# Channel_Power.net
KiCad netlist of a schematic drawn in Altium Designer
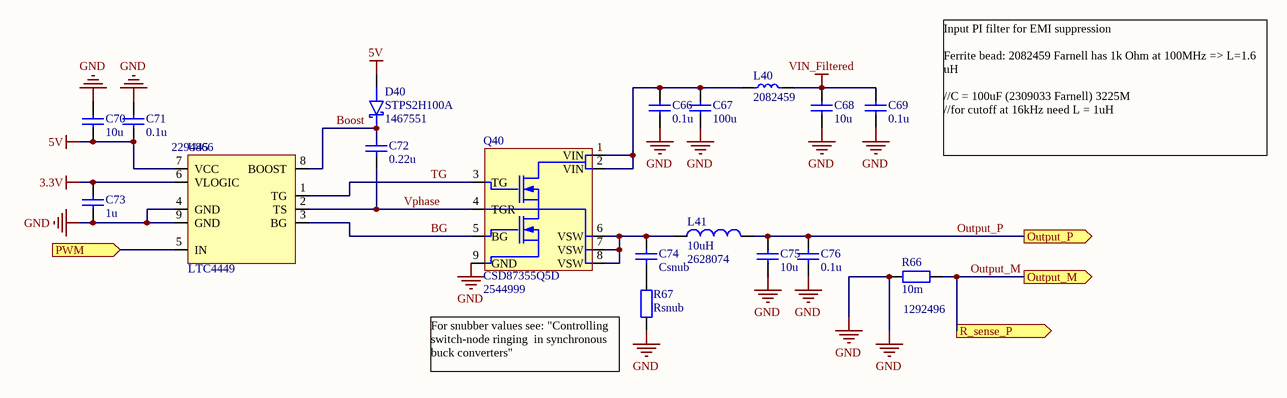
[diagram p0: Channel_Power.SchDoc]

(export (version "E")
  (design (tool "Eeschema 10.0.6"))
  (components
    (comp (ref "C66") (value "0.1u") (footprint "CAPC1608M") (libsource (lib "Passives") (part "C")))
    (comp (ref "C67") (value "100u") (footprint "CAPC3225M") (libsource (lib "Passives") (part "C")))
    (comp (ref "C68") (value "10u") (footprint "CAPC2012M") (libsource (lib "Passives") (part "C")))
    (comp (ref "C69") (value "0.1u") (footprint "CAPC1608M") (libsource (lib "Passives") (part "C")))
    (comp (ref "C70") (value "10u") (footprint "CAPC2012M") (libsource (lib "Passives") (part "C")))
    (comp (ref "C71") (value "0.1u") (footprint "CAPC1608M") (libsource (lib "Passives") (part "C")))
    (comp (ref "C72") (value "0.22u") (footprint "CAPC1608M") (libsource (lib "Passives") (part "C")))
    (comp (ref "C73") (value "1u") (footprint "CAPC1608M") (libsource (lib "Passives") (part "C")))
    (comp (ref "C74") (value "Csnub") (footprint "CAPC1608M") (libsource (lib "Passives") (part "C")))
    (comp (ref "C75") (value "10u") (footprint "CAPC2012M") (libsource (lib "Passives") (part "C")))
    (comp (ref "C76") (value "0.1u") (footprint "CAPC1608M") (libsource (lib "Passives") (part "C")))
    (comp (ref "D40")
      (value "STPS2H100A")
      (footprint "DSO-C2/X1.8")
      (description "Shottky rectifier")
      (fields (field (name "SUPPLIER PART NUMBER 1") "1467551"))
      (libsource (lib "Diodes") (part "STPS2H100A"))
    )
    (comp (ref "L40")
      (value "Wurth_742792901")
      (footprint "WE_742792901")
      (description "Ferrite bead, 1.1k Ohm, 10A, (Wurth 742792901)")
      (fields (field (name "SUPPLIER PART NUMBER 1") "2082459"))
      (libsource (lib "Passives") (part "Wurth_742792901"))
    )
    (comp (ref "L41")
      (value "10uH")
      (footprint "L_XAL1510")
      (description "XAL1510 Series inductor")
      (fields (field (name "SUPPLIER PART NUMBER 1") "2628074"))
      (libsource (lib "Passives") (part "L_XAL1510"))
    )
    (comp (ref "Q40")
      (value "CSD87355Q5D")
      (footprint "SON-8")
      (description "Synchronous Buck NexFET Power Block")
      (fields (field (name "SUPPLIER PART NUMBER 1") "2544999"))
      (libsource (lib "Linear") (part "CSD87355Q5D"))
    )
    (comp (ref "R66") (value "10m") (footprint "RESC6432M") (libsource (lib "Passives") (part "R")))
    (comp (ref "R67") (value "Rsnub") (footprint "RESC1608M") (libsource (lib "Passives") (part "R")))
    (comp (ref "U45")
      (value "LTC4449")
      (footprint "DFN-8")
      (description "High Speed Synchronous N-Channel MOSFET Driver")
      (fields (field (name "SUPPLIER PART NUMBER 1") "2294866"))
      (libsource (lib "Controllers") (part "LTC4449"))
    )
  )
  (nets
    (net (code "1") (name "/BG") (class "Default")
      (node (ref "Q40") (pin "5") (pinfunction "BG_5") (pintype "passive"))
      (node (ref "U45") (pin "3") (pinfunction "BG_3") (pintype "passive"))
    )
    (net (code "2") (name "/Boost") (class "Default")
      (node (ref "C72") (pin "1") (pinfunction "1_1") (pintype "passive"))
      (node (ref "D40") (pin "C") (pinfunction "C_C") (pintype "passive"))
      (node (ref "U45") (pin "8") (pinfunction "BOOST_8") (pintype "passive"))
    )
    (net (code "3") (name "/Output_M") (class "Default")
      (node (ref "R66") (pin "2") (pinfunction "2_2") (pintype "passive"))
    )
    (net (code "4") (name "/Output_P") (class "Default")
      (node (ref "C75") (pin "1") (pinfunction "1_1") (pintype "passive"))
      (node (ref "C76") (pin "1") (pinfunction "1_1") (pintype "passive"))
      (node (ref "L41") (pin "1") (pintype "passive"))
    )
    (net (code "5") (name "/PWM") (class "Default")
      (node (ref "U45") (pin "5") (pinfunction "IN_5") (pintype "passive"))
    )
    (net (code "6") (name "/TG") (class "Default")
      (node (ref "Q40") (pin "3") (pinfunction "TG_3") (pintype "passive"))
      (node (ref "U45") (pin "1") (pinfunction "TG_1") (pintype "passive"))
    )
    (net (code "7") (name "/Vphase") (class "Default")
      (node (ref "C72") (pin "2") (pinfunction "2_2") (pintype "passive"))
      (node (ref "Q40") (pin "4") (pinfunction "TGR_4") (pintype "passive"))
      (node (ref "U45") (pin "2") (pinfunction "TS_2") (pintype "passive"))
    )
    (net (code "8") (name "3.3V") (class "Default")
      (node (ref "C73") (pin "1") (pinfunction "1_1") (pintype "passive"))
      (node (ref "U45") (pin "6") (pinfunction "VLOGIC_6") (pintype "passive"))
    )
    (net (code "9") (name "5V") (class "Default")
      (node (ref "C70") (pin "2") (pinfunction "2_2") (pintype "passive"))
      (node (ref "C71") (pin "2") (pinfunction "2_2") (pintype "passive"))
      (node (ref "D40") (pin "A") (pinfunction "A_A") (pintype "passive"))
      (node (ref "U45") (pin "7") (pinfunction "VCC_7") (pintype "passive"))
    )
    (net (code "10") (name "GND") (class "Default")
      (node (ref "C66") (pin "2") (pinfunction "2_2") (pintype "passive"))
      (node (ref "C67") (pin "2") (pinfunction "2_2") (pintype "passive"))
      (node (ref "C68") (pin "2") (pinfunction "2_2") (pintype "passive"))
      (node (ref "C69") (pin "2") (pinfunction "2_2") (pintype "passive"))
      (node (ref "C70") (pin "1") (pinfunction "1_1") (pintype "passive"))
      (node (ref "C71") (pin "1") (pinfunction "1_1") (pintype "passive"))
      (node (ref "C73") (pin "2") (pinfunction "2_2") (pintype "passive"))
      (node (ref "C75") (pin "2") (pinfunction "2_2") (pintype "passive"))
      (node (ref "C76") (pin "2") (pinfunction "2_2") (pintype "passive"))
      (node (ref "Q40") (pin "9") (pinfunction "GND_9") (pintype "passive"))
      (node (ref "R66") (pin "1") (pinfunction "1_1") (pintype "passive"))
      (node (ref "R67") (pin "1") (pinfunction "1_1") (pintype "passive"))
      (node (ref "U45") (pin "4") (pinfunction "GND_4") (pintype "passive"))
      (node (ref "U45") (pin "9") (pinfunction "GND_9") (pintype "passive"))
    )
    (net (code "11") (name "Net-(C66-Pad1)") (class "Default")
      (node (ref "C66") (pin "1") (pinfunction "1_1") (pintype "passive"))
      (node (ref "C67") (pin "1") (pinfunction "1_1") (pintype "passive"))
      (node (ref "L40") (pin "1") (pinfunction "1_1") (pintype "passive"))
      (node (ref "Q40") (pin "1") (pinfunction "VIN_1") (pintype "passive"))
      (node (ref "Q40") (pin "2") (pinfunction "VIN_2") (pintype "passive"))
    )
    (net (code "12") (name "Net-(C74-Pad1)") (class "Default")
      (node (ref "C74") (pin "1") (pinfunction "1_1") (pintype "passive"))
      (node (ref "L41") (pin "2") (pintype "passive"))
      (node (ref "Q40") (pin "6") (pinfunction "VSW_6") (pintype "passive"))
      (node (ref "Q40") (pin "7") (pinfunction "VSW_7") (pintype "passive"))
      (node (ref "Q40") (pin "8") (pinfunction "VSW_8") (pintype "passive"))
    )
    (net (code "13") (name "Net-(C74-Pad2)") (class "Default")
      (node (ref "C74") (pin "2") (pinfunction "2_2") (pintype "passive"))
      (node (ref "R67") (pin "2") (pinfunction "2_2") (pintype "passive"))
    )
    (net (code "14") (name "VIN_Filtered") (class "Default")
      (node (ref "C68") (pin "1") (pinfunction "1_1") (pintype "passive"))
      (node (ref "C69") (pin "1") (pinfunction "1_1") (pintype "passive"))
      (node (ref "L40") (pin "2") (pinfunction "2_2") (pintype "passive"))
    )
  )
)
